# CPU_Power_XTAL_Prog.net
KiCad netlist of a schematic drawn in Altium Designer
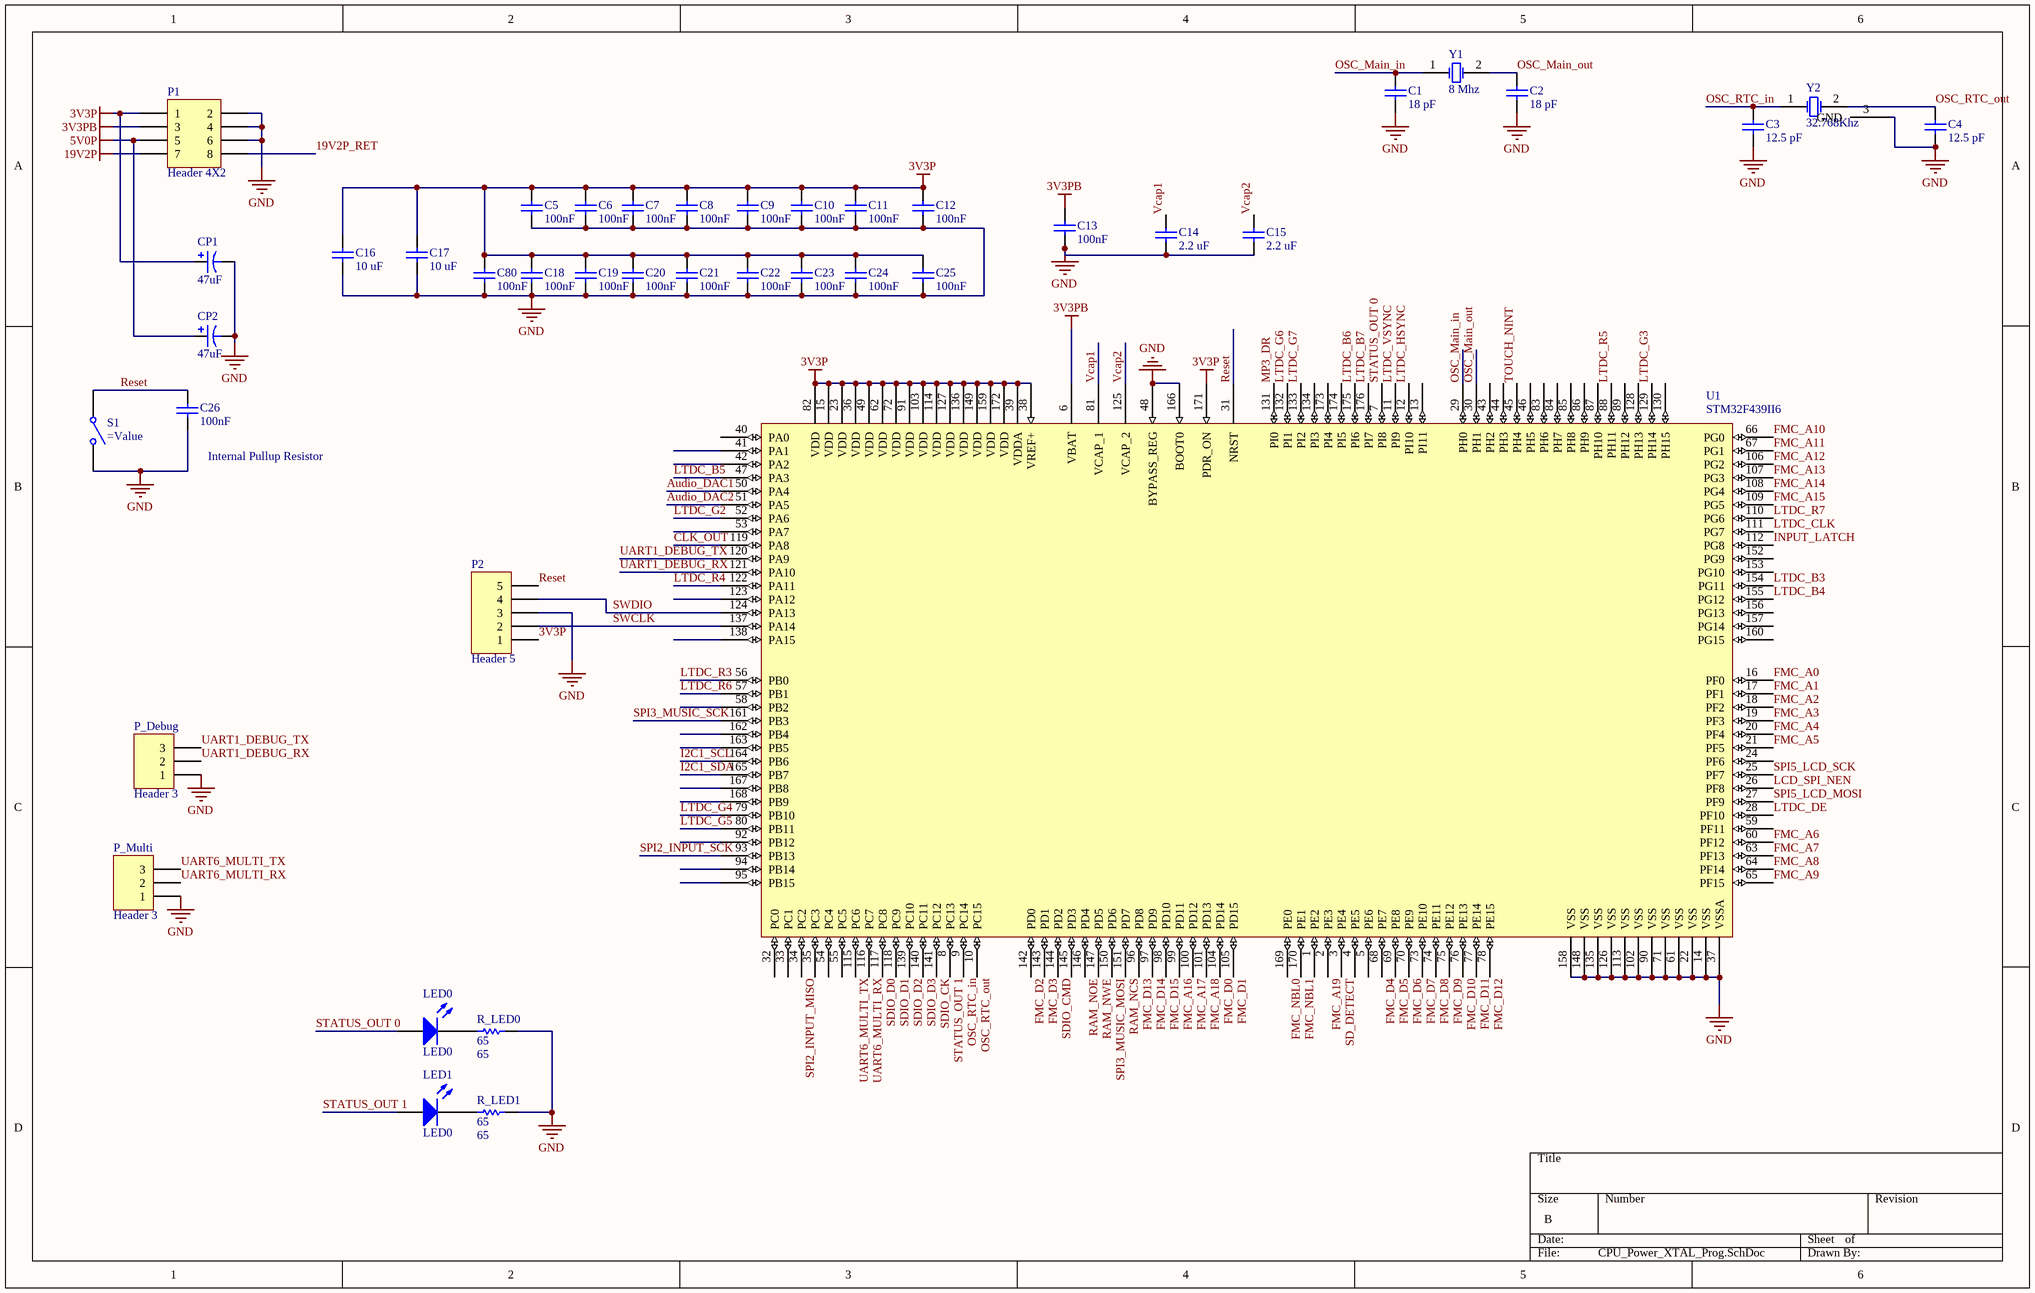
[diagram p0: CPU_Power_XTAL_Prog.SchDoc]

(export (version "E")
  (design (tool "Eeschema 10.0.6"))
  (components
    (comp (ref "C1")
      (value "18 pF")
      (footprint "C0805")
      (description "Capacitor")
      (fields (field (name "PUBLISHER") "Altium Limited"))
      (libsource (lib "Miscellaneous Devices") (part "Cap"))
    )
    (comp (ref "C2")
      (value "18 pF")
      (footprint "C0805")
      (description "Capacitor")
      (fields (field (name "PUBLISHER") "Altium Limited"))
      (libsource (lib "Miscellaneous Devices") (part "Cap"))
    )
    (comp (ref "C3")
      (value "12.5 pF")
      (footprint "C0805")
      (description "Capacitor")
      (fields (field (name "PUBLISHER") "Altium Limited"))
      (libsource (lib "Miscellaneous Devices") (part "Cap"))
    )
    (comp (ref "C4")
      (value "12.5 pF")
      (footprint "C0805")
      (description "Capacitor")
      (fields (field (name "PUBLISHER") "Altium Limited"))
      (libsource (lib "Miscellaneous Devices") (part "Cap"))
    )
    (comp (ref "C5")
      (value "100nF")
      (footprint "C0805")
      (description "Capacitor")
      (fields (field (name "PUBLISHER") "Altium Limited"))
      (libsource (lib "Miscellaneous Devices") (part "Cap"))
    )
    (comp (ref "C6")
      (value "100nF")
      (footprint "C0805")
      (description "Capacitor")
      (fields (field (name "PUBLISHER") "Altium Limited"))
      (libsource (lib "Miscellaneous Devices") (part "Cap"))
    )
    (comp (ref "C7")
      (value "100nF")
      (footprint "C0805")
      (description "Capacitor")
      (fields (field (name "PUBLISHER") "Altium Limited"))
      (libsource (lib "Miscellaneous Devices") (part "Cap"))
    )
    (comp (ref "C8")
      (value "100nF")
      (footprint "C0805")
      (description "Capacitor")
      (fields (field (name "PUBLISHER") "Altium Limited"))
      (libsource (lib "Miscellaneous Devices") (part "Cap"))
    )
    (comp (ref "C9")
      (value "100nF")
      (footprint "C0805")
      (description "Capacitor")
      (fields (field (name "PUBLISHER") "Altium Limited"))
      (libsource (lib "Miscellaneous Devices") (part "Cap"))
    )
    (comp (ref "C10")
      (value "100nF")
      (footprint "C0805")
      (description "Capacitor")
      (fields (field (name "PUBLISHER") "Altium Limited"))
      (libsource (lib "Miscellaneous Devices") (part "Cap"))
    )
    (comp (ref "C11")
      (value "100nF")
      (footprint "C0805")
      (description "Capacitor")
      (fields (field (name "PUBLISHER") "Altium Limited"))
      (libsource (lib "Miscellaneous Devices") (part "Cap"))
    )
    (comp (ref "C12")
      (value "100nF")
      (footprint "C0805")
      (description "Capacitor")
      (fields (field (name "PUBLISHER") "Altium Limited"))
      (libsource (lib "Miscellaneous Devices") (part "Cap"))
    )
    (comp (ref "C13")
      (value "100nF")
      (footprint "C0805")
      (description "Capacitor")
      (fields (field (name "PUBLISHER") "Altium Limited"))
      (libsource (lib "Miscellaneous Devices") (part "Cap"))
    )
    (comp (ref "C14")
      (value "2.2 uF")
      (footprint "C0805")
      (description "Capacitor")
      (fields (field (name "PUBLISHER") "Altium Limited"))
      (libsource (lib "Miscellaneous Devices") (part "Cap"))
    )
    (comp (ref "C15")
      (value "2.2 uF")
      (footprint "C0805")
      (description "Capacitor")
      (fields (field (name "PUBLISHER") "Altium Limited"))
      (libsource (lib "Miscellaneous Devices") (part "Cap"))
    )
    (comp (ref "C16")
      (value "10 uF")
      (footprint "C0805")
      (description "Capacitor")
      (fields (field (name "PUBLISHER") "Altium Limited"))
      (libsource (lib "Miscellaneous Devices") (part "Cap"))
    )
    (comp (ref "C17")
      (value "10 uF")
      (footprint "C0805")
      (description "Capacitor")
      (fields (field (name "PUBLISHER") "Altium Limited"))
      (libsource (lib "Miscellaneous Devices") (part "Cap"))
    )
    (comp (ref "C18")
      (value "100nF")
      (footprint "C0805")
      (description "Capacitor")
      (fields (field (name "PUBLISHER") "Altium Limited"))
      (libsource (lib "Miscellaneous Devices") (part "Cap"))
    )
    (comp (ref "C19")
      (value "100nF")
      (footprint "C0805")
      (description "Capacitor")
      (fields (field (name "PUBLISHER") "Altium Limited"))
      (libsource (lib "Miscellaneous Devices") (part "Cap"))
    )
    (comp (ref "C20")
      (value "100nF")
      (footprint "C0805")
      (description "Capacitor")
      (fields (field (name "PUBLISHER") "Altium Limited"))
      (libsource (lib "Miscellaneous Devices") (part "Cap"))
    )
    (comp (ref "C21")
      (value "100nF")
      (footprint "C0805")
      (description "Capacitor")
      (fields (field (name "PUBLISHER") "Altium Limited"))
      (libsource (lib "Miscellaneous Devices") (part "Cap"))
    )
    (comp (ref "C22")
      (value "100nF")
      (footprint "C0805")
      (description "Capacitor")
      (fields (field (name "PUBLISHER") "Altium Limited"))
      (libsource (lib "Miscellaneous Devices") (part "Cap"))
    )
    (comp (ref "C23")
      (value "100nF")
      (footprint "C0805")
      (description "Capacitor")
      (fields (field (name "PUBLISHER") "Altium Limited"))
      (libsource (lib "Miscellaneous Devices") (part "Cap"))
    )
    (comp (ref "C24")
      (value "100nF")
      (footprint "C0805")
      (description "Capacitor")
      (fields (field (name "PUBLISHER") "Altium Limited"))
      (libsource (lib "Miscellaneous Devices") (part "Cap"))
    )
    (comp (ref "C25")
      (value "100nF")
      (footprint "C0805")
      (description "Capacitor")
      (fields (field (name "PUBLISHER") "Altium Limited"))
      (libsource (lib "Miscellaneous Devices") (part "Cap"))
    )
    (comp (ref "C26")
      (value "100nF")
      (footprint "C0805")
      (description "Capacitor")
      (fields (field (name "PUBLISHER") "Altium Limited"))
      (libsource (lib "Miscellaneous Devices") (part "Cap"))
    )
    (comp (ref "C80")
      (value "100nF")
      (footprint "C0805")
      (description "Capacitor")
      (fields (field (name "PUBLISHER") "Altium Limited"))
      (libsource (lib "Miscellaneous Devices") (part "Cap"))
    )
    (comp (ref "CP1")
      (value "47uF")
      (footprint "KemetC3")
      (description "Polarized Capacitor (Radial)")
      (fields (field (name "PUBLISHER") "Altium Limited"))
      (libsource (lib "Miscellaneous Devices") (part "Cap Pol1"))
    )
    (comp (ref "CP2")
      (value "47uF")
      (footprint "KemetC3")
      (description "Polarized Capacitor (Radial)")
      (fields (field (name "PUBLISHER") "Altium Limited"))
      (libsource (lib "Miscellaneous Devices") (part "Cap Pol1"))
    )
    (comp (ref "LED0")
      (value "LED0")
      (footprint "LED-LTST")
      (description "Typical INFRARED GaAs LED")
      (fields (field (name "PUBLISHER") "Altium Limited"))
      (libsource (lib "Miscellaneous Devices") (part "LED0"))
    )
    (comp (ref "LED1")
      (value "LED0")
      (footprint "LED-LTST")
      (description "Typical INFRARED GaAs LED")
      (fields (field (name "PUBLISHER") "Altium Limited"))
      (libsource (lib "Miscellaneous Devices") (part "LED0"))
    )
    (comp (ref "P1")
      (value "Header 4X2")
      (footprint "Molex MiniFit Jr8")
      (description "Header, 4-Pin, Dual row")
      (fields (field (name "PUBLISHER") "Altium Limited"))
      (libsource (lib "Miscellaneous Connectors") (part "Header 4X2"))
    )
    (comp (ref "P2")
      (value "Header 5")
      (footprint "HDR1X5")
      (description "Header, 5-Pin")
      (fields (field (name "PUBLISHER") "Altium Limited"))
      (libsource (lib "Miscellaneous Connectors") (part "Header 5"))
    )
    (comp (ref "P_Debug")
      (value "Header 3")
      (footprint "HDR1X3")
      (description "Header, 3-Pin")
      (fields (field (name "PUBLISHER") "Altium Limited"))
      (libsource (lib "Miscellaneous Connectors") (part "Header 3"))
    )
    (comp (ref "P_Multi")
      (value "Header 3")
      (footprint "HDR1X3")
      (description "Header, 3-Pin")
      (fields (field (name "PUBLISHER") "Altium Limited"))
      (libsource (lib "Miscellaneous Connectors") (part "Header 3"))
    )
    (comp (ref "R_LED0")
      (value "65")
      (footprint "6-0805_M")
      (description "Resistor")
      (fields (field (name "ALTIUM_VALUE") "65") (field (name "PUBLISHER") "Altium Limited"))
      (libsource (lib "Miscellaneous Devices") (part "Res1"))
    )
    (comp (ref "R_LED1")
      (value "65")
      (footprint "6-0805_M")
      (description "Resistor")
      (fields (field (name "ALTIUM_VALUE") "65") (field (name "PUBLISHER") "Altium Limited"))
      (libsource (lib "Miscellaneous Devices") (part "Res1"))
    )
    (comp (ref "S1")
      (value "~")
      (footprint "Reset_Button")
      (description "Single-Pole, Single-Throw Switch")
      (fields (field (name "PUBLISHER") "Altium Limited"))
      (libsource (lib "Miscellaneous Devices") (part "SW-SPST"))
    )
    (comp (ref "U1")
      (value "STM32F439II6")
      (footprint "LQFP76")
      (description "Arm Cortex M4 Processor")
      (libsource (lib "GameMan") (part "STM32F439IIT6"))
    )
    (comp (ref "Y1")
      (value "8 Mhz")
      (footprint "HC-49U")
      (description "Crystal Oscillator")
      (fields (field (name "PUBLISHER") "Altium Limited"))
      (libsource (lib "Miscellaneous Devices") (part "XTAL"))
    )
    (comp (ref "Y2")
      (value "32.768Khz")
      (footprint "C-2Type Crystal")
      (description "Crystal Oscillator")
      (fields (field (name "PUBLISHER") "Altium Limited"))
      (libsource (lib "") (part "XTAL_1"))
    )
  )
  (nets
    (net (code "1") (name "/19V2P_RET") (class "Default")
      (node (ref "P1") (pin "8") (pinfunction "8_8") (pintype "passive"))
    )
    (net (code "2") (name "/Audio_DAC1") (class "Default")
      (node (ref "U1") (pin "50") (pinfunction "PA4_50") (pintype "bidirectional"))
    )
    (net (code "3") (name "/Audio_DAC2") (class "Default")
      (node (ref "U1") (pin "51") (pinfunction "PA5_51") (pintype "bidirectional"))
    )
    (net (code "4") (name "/CLK_OUT") (class "Default")
      (node (ref "U1") (pin "119") (pinfunction "PA8_119") (pintype "bidirectional"))
    )
    (net (code "5") (name "/FMC_A0") (class "Default")
      (node (ref "U1") (pin "16") (pinfunction "PF0_16") (pintype "bidirectional"))
    )
    (net (code "6") (name "/FMC_A1") (class "Default")
      (node (ref "U1") (pin "17") (pinfunction "PF1_17") (pintype "bidirectional"))
    )
    (net (code "7") (name "/FMC_A2") (class "Default")
      (node (ref "U1") (pin "18") (pinfunction "PF2_18") (pintype "bidirectional"))
    )
    (net (code "8") (name "/FMC_A3") (class "Default")
      (node (ref "U1") (pin "19") (pinfunction "PF3_19") (pintype "bidirectional"))
    )
    (net (code "9") (name "/FMC_A4") (class "Default")
      (node (ref "U1") (pin "20") (pinfunction "PF4_20") (pintype "bidirectional"))
    )
    (net (code "10") (name "/FMC_A5") (class "Default")
      (node (ref "U1") (pin "21") (pinfunction "PF5_21") (pintype "bidirectional"))
    )
    (net (code "11") (name "/FMC_A6") (class "Default")
      (node (ref "U1") (pin "60") (pinfunction "PF12_60") (pintype "bidirectional"))
    )
    (net (code "12") (name "/FMC_A7") (class "Default")
      (node (ref "U1") (pin "63") (pinfunction "PF13_63") (pintype "bidirectional"))
    )
    (net (code "13") (name "/FMC_A8") (class "Default")
      (node (ref "U1") (pin "64") (pinfunction "PF14_64") (pintype "bidirectional"))
    )
    (net (code "14") (name "/FMC_A9") (class "Default")
      (node (ref "U1") (pin "65") (pinfunction "PF15_65") (pintype "bidirectional"))
    )
    (net (code "15") (name "/FMC_A10") (class "Default")
      (node (ref "U1") (pin "66") (pinfunction "PG0_66") (pintype "bidirectional"))
    )
    (net (code "16") (name "/FMC_A11") (class "Default")
      (node (ref "U1") (pin "67") (pinfunction "PG1_67") (pintype "bidirectional"))
    )
    (net (code "17") (name "/FMC_A12") (class "Default")
      (node (ref "U1") (pin "106") (pinfunction "PG2_106") (pintype "bidirectional"))
    )
    (net (code "18") (name "/FMC_A13") (class "Default")
      (node (ref "U1") (pin "107") (pinfunction "PG3_107") (pintype "bidirectional"))
    )
    (net (code "19") (name "/FMC_A14") (class "Default")
      (node (ref "U1") (pin "108") (pinfunction "PG4_108") (pintype "bidirectional"))
    )
    (net (code "20") (name "/FMC_A15") (class "Default")
      (node (ref "U1") (pin "109") (pinfunction "PG5_109") (pintype "bidirectional"))
    )
    (net (code "21") (name "/FMC_A16") (class "Default")
      (node (ref "U1") (pin "99") (pinfunction "PD11_99") (pintype "bidirectional"))
    )
    (net (code "22") (name "/FMC_A17") (class "Default")
      (node (ref "U1") (pin "100") (pinfunction "PD12_100") (pintype "bidirectional"))
    )
    (net (code "23") (name "/FMC_A18") (class "Default")
      (node (ref "U1") (pin "101") (pinfunction "PD13_101") (pintype "bidirectional"))
    )
    (net (code "24") (name "/FMC_A19") (class "Default")
      (node (ref "U1") (pin "2") (pinfunction "PE3_2") (pintype "bidirectional"))
    )
    (net (code "25") (name "/FMC_D0") (class "Default")
      (node (ref "U1") (pin "104") (pinfunction "PD14_104") (pintype "bidirectional"))
    )
    (net (code "26") (name "/FMC_D1") (class "Default")
      (node (ref "U1") (pin "105") (pinfunction "PD15_105") (pintype "bidirectional"))
    )
    (net (code "27") (name "/FMC_D2") (class "Default")
      (node (ref "U1") (pin "142") (pinfunction "PD0_142") (pintype "bidirectional"))
    )
    (net (code "28") (name "/FMC_D3") (class "Default")
      (node (ref "U1") (pin "143") (pinfunction "PD1_143") (pintype "bidirectional"))
    )
    (net (code "29") (name "/FMC_D4") (class "Default")
      (node (ref "U1") (pin "68") (pinfunction "PE7_68") (pintype "bidirectional"))
    )
    (net (code "30") (name "/FMC_D5") (class "Default")
      (node (ref "U1") (pin "69") (pinfunction "PE8_69") (pintype "bidirectional"))
    )
    (net (code "31") (name "/FMC_D6") (class "Default")
      (node (ref "U1") (pin "70") (pinfunction "PE9_70") (pintype "bidirectional"))
    )
    (net (code "32") (name "/FMC_D7") (class "Default")
      (node (ref "U1") (pin "73") (pinfunction "PE10_73") (pintype "bidirectional"))
    )
    (net (code "33") (name "/FMC_D8") (class "Default")
      (node (ref "U1") (pin "74") (pinfunction "PE11_74") (pintype "bidirectional"))
    )
    (net (code "34") (name "/FMC_D9") (class "Default")
      (node (ref "U1") (pin "75") (pinfunction "PE12_75") (pintype "bidirectional"))
    )
    (net (code "35") (name "/FMC_D10") (class "Default")
      (node (ref "U1") (pin "76") (pinfunction "PE13_76") (pintype "bidirectional"))
    )
    (net (code "36") (name "/FMC_D11") (class "Default")
      (node (ref "U1") (pin "77") (pinfunction "PE14_77") (pintype "bidirectional"))
    )
    (net (code "37") (name "/FMC_D12") (class "Default")
      (node (ref "U1") (pin "78") (pinfunction "PE15_78") (pintype "bidirectional"))
    )
    (net (code "38") (name "/FMC_D13") (class "Default")
      (node (ref "U1") (pin "96") (pinfunction "PD8_96") (pintype "bidirectional"))
    )
    (net (code "39") (name "/FMC_D14") (class "Default")
      (node (ref "U1") (pin "97") (pinfunction "PD9_97") (pintype "bidirectional"))
    )
    (net (code "40") (name "/FMC_D15") (class "Default")
      (node (ref "U1") (pin "98") (pinfunction "PD10_98") (pintype "bidirectional"))
    )
    (net (code "41") (name "/FMC_NBL0") (class "Default")
      (node (ref "U1") (pin "169") (pinfunction "PE0_169") (pintype "bidirectional"))
    )
    (net (code "42") (name "/FMC_NBL1") (class "Default")
      (node (ref "U1") (pin "170") (pinfunction "PE1_170") (pintype "bidirectional"))
    )
    (net (code "43") (name "/I2C1_SCL") (class "Default")
      (node (ref "U1") (pin "164") (pinfunction "PB6_164") (pintype "bidirectional"))
    )
    (net (code "44") (name "/I2C1_SDA") (class "Default")
      (node (ref "U1") (pin "165") (pinfunction "PB7_165") (pintype "bidirectional"))
    )
    (net (code "45") (name "/INPUT_LATCH") (class "Default")
      (node (ref "U1") (pin "112") (pinfunction "PG8_112") (pintype "bidirectional"))
    )
    (net (code "46") (name "/LCD_SPI_NEN") (class "Default")
      (node (ref "U1") (pin "26") (pinfunction "PF8_26") (pintype "bidirectional"))
    )
    (net (code "47") (name "/LTDC_B3") (class "Default")
      (node (ref "U1") (pin "154") (pinfunction "PG11_154") (pintype "bidirectional"))
    )
    (net (code "48") (name "/LTDC_B4") (class "Default")
      (node (ref "U1") (pin "155") (pinfunction "PG12_155") (pintype "bidirectional"))
    )
    (net (code "49") (name "/LTDC_B5") (class "Default")
      (node (ref "U1") (pin "47") (pinfunction "PA3_47") (pintype "bidirectional"))
    )
    (net (code "50") (name "/LTDC_B6") (class "Default")
      (node (ref "U1") (pin "175") (pinfunction "PI6_175") (pintype "bidirectional"))
    )
    (net (code "51") (name "/LTDC_B7") (class "Default")
      (node (ref "U1") (pin "176") (pinfunction "PI7_176") (pintype "bidirectional"))
    )
    (net (code "52") (name "/LTDC_CLK") (class "Default")
      (node (ref "U1") (pin "111") (pinfunction "PG7_111") (pintype "bidirectional"))
    )
    (net (code "53") (name "/LTDC_DE") (class "Default")
      (node (ref "U1") (pin "28") (pinfunction "PF10_28") (pintype "bidirectional"))
    )
    (net (code "54") (name "/LTDC_G2") (class "Default")
      (node (ref "U1") (pin "52") (pinfunction "PA6_52") (pintype "bidirectional"))
    )
    (net (code "55") (name "/LTDC_G3") (class "Default")
      (node (ref "U1") (pin "129") (pinfunction "PH14_129") (pintype "bidirectional"))
    )
    (net (code "56") (name "/LTDC_G4") (class "Default")
      (node (ref "U1") (pin "79") (pinfunction "PB10_79") (pintype "bidirectional"))
    )
    (net (code "57") (name "/LTDC_G5") (class "Default")
      (node (ref "U1") (pin "80") (pinfunction "PB11_80") (pintype "bidirectional"))
    )
    (net (code "58") (name "/LTDC_G6") (class "Default")
      (node (ref "U1") (pin "132") (pinfunction "PI1_132") (pintype "bidirectional"))
    )
    (net (code "59") (name "/LTDC_G7") (class "Default")
      (node (ref "U1") (pin "133") (pinfunction "PI2_133") (pintype "bidirectional"))
    )
    (net (code "60") (name "/LTDC_HSYNC") (class "Default")
      (node (ref "U1") (pin "12") (pinfunction "PI10_12") (pintype "bidirectional"))
    )
    (net (code "61") (name "/LTDC_R3") (class "Default")
      (node (ref "U1") (pin "56") (pinfunction "PB0_56") (pintype "bidirectional"))
    )
    (net (code "62") (name "/LTDC_R4") (class "Default")
      (node (ref "U1") (pin "122") (pinfunction "PA11_122") (pintype "bidirectional"))
    )
    (net (code "63") (name "/LTDC_R5") (class "Default")
      (node (ref "U1") (pin "88") (pinfunction "PH11_88") (pintype "bidirectional"))
    )
    (net (code "64") (name "/LTDC_R6") (class "Default")
      (node (ref "U1") (pin "57") (pinfunction "PB1_57") (pintype "bidirectional"))
    )
    (net (code "65") (name "/LTDC_R7") (class "Default")
      (node (ref "U1") (pin "110") (pinfunction "PG6_110") (pintype "bidirectional"))
    )
    (net (code "66") (name "/LTDC_VSYNC") (class "Default")
      (node (ref "U1") (pin "11") (pinfunction "PI9_11") (pintype "bidirectional"))
    )
    (net (code "67") (name "/MP3_DR") (class "Default")
      (node (ref "U1") (pin "131") (pinfunction "PI0_131") (pintype "bidirectional"))
    )
    (net (code "68") (name "/OSC_Main_in") (class "Default")
      (node (ref "C1") (pin "2") (pinfunction "2_2") (pintype "passive"))
      (node (ref "U1") (pin "29") (pinfunction "PH0_29") (pintype "bidirectional"))
      (node (ref "Y1") (pin "1") (pinfunction "OSC1_1") (pintype "passive"))
    )
    (net (code "69") (name "/OSC_Main_out") (class "Default")
      (node (ref "C2") (pin "2") (pinfunction "2_2") (pintype "passive"))
      (node (ref "U1") (pin "30") (pinfunction "PH1_30") (pintype "bidirectional"))
      (node (ref "Y1") (pin "2") (pinfunction "OSC2_2") (pintype "passive"))
    )
    (net (code "70") (name "/OSC_RTC_in") (class "Default")
      (node (ref "C3") (pin "2") (pinfunction "2_2") (pintype "passive"))
      (node (ref "U1") (pin "9") (pinfunction "PC14_9") (pintype "bidirectional"))
      (node (ref "Y2") (pin "1") (pinfunction "OSC1_1") (pintype "passive"))
    )
    (net (code "71") (name "/OSC_RTC_out") (class "Default")
      (node (ref "C4") (pin "2") (pinfunction "2_2") (pintype "passive"))
      (node (ref "U1") (pin "10") (pinfunction "PC15_10") (pintype "bidirectional"))
      (node (ref "Y2") (pin "2") (pinfunction "OSC2_2") (pintype "passive"))
    )
    (net (code "72") (name "/RAM_NCS") (class "Default")
      (node (ref "U1") (pin "151") (pinfunction "PD7_151") (pintype "bidirectional"))
    )
    (net (code "73") (name "/RAM_NOE") (class "Default")
      (node (ref "U1") (pin "146") (pinfunction "PD4_146") (pintype "bidirectional"))
    )
    (net (code "74") (name "/RAM_NWE") (class "Default")
      (node (ref "U1") (pin "147") (pinfunction "PD5_147") (pintype "bidirectional"))
    )
    (net (code "75") (name "/Reset") (class "Default")
      (node (ref "C26") (pin "2") (pinfunction "2_2") (pintype "passive"))
      (node (ref "P2") (pin "5") (pinfunction "5_5") (pintype "passive"))
      (node (ref "S1") (pin "0") (pinfunction "COMMON_0") (pintype "passive"))
      (node (ref "U1") (pin "31") (pinfunction "NRST_31") (pintype "power_in"))
    )
    (net (code "76") (name "/SDIO_CK") (class "Default")
      (node (ref "U1") (pin "141") (pinfunction "PC12_141") (pintype "bidirectional"))
    )
    (net (code "77") (name "/SDIO_CMD") (class "Default")
      (node (ref "U1") (pin "144") (pinfunction "PD2_144") (pintype "bidirectional"))
    )
    (net (code "78") (name "/SDIO_D0") (class "Default")
      (node (ref "U1") (pin "117") (pinfunction "PC8_117") (pintype "bidirectional"))
    )
    (net (code "79") (name "/SDIO_D1") (class "Default")
      (node (ref "U1") (pin "118") (pinfunction "PC9_118") (pintype "bidirectional"))
    )
    (net (code "80") (name "/SDIO_D2") (class "Default")
      (node (ref "U1") (pin "139") (pinfunction "PC10_139") (pintype "bidirectional"))
    )
    (net (code "81") (name "/SDIO_D3") (class "Default")
      (node (ref "U1") (pin "140") (pinfunction "PC11_140") (pintype "bidirectional"))
    )
    (net (code "82") (name "/SD_DETECT") (class "Default")
      (node (ref "U1") (pin "3") (pinfunction "PE4_3") (pintype "bidirectional"))
    )
    (net (code "83") (name "/SPI2_INPUT_MISO") (class "Default")
      (node (ref "U1") (pin "34") (pinfunction "PC2_34") (pintype "bidirectional"))
    )
    (net (code "84") (name "/SPI2_INPUT_SCK") (class "Default")
      (node (ref "U1") (pin "93") (pinfunction "PB13_93") (pintype "bidirectional"))
    )
    (net (code "85") (name "/SPI3_MUSIC_MOSI") (class "Default")
      (node (ref "U1") (pin "150") (pinfunction "PD6_150") (pintype "bidirectional"))
    )
    (net (code "86") (name "/SPI3_MUSIC_SCK") (class "Default")
      (node (ref "U1") (pin "161") (pinfunction "PB3_161") (pintype "bidirectional"))
    )
    (net (code "87") (name "/SPI5_LCD_MOSI") (class "Default")
      (node (ref "U1") (pin "27") (pinfunction "PF9_27") (pintype "bidirectional"))
    )
    (net (code "88") (name "/SPI5_LCD_SCK") (class "Default")
      (node (ref "U1") (pin "25") (pinfunction "PF7_25") (pintype "bidirectional"))
    )
    (net (code "89") (name "/STATUS_OUT 0") (class "Default")
      (node (ref "LED0") (pin "A") (pinfunction "A_A") (pintype "passive"))
      (node (ref "U1") (pin "7") (pinfunction "PI8_7") (pintype "bidirectional"))
    )
    (net (code "90") (name "/STATUS_OUT 1") (class "Default")
      (node (ref "LED1") (pin "A") (pinfunction "A_A") (pintype "passive"))
      (node (ref "U1") (pin "8") (pinfunction "PC13_8") (pintype "bidirectional"))
    )
    (net (code "91") (name "/SWCLK") (class "Default")
      (node (ref "P2") (pin "2") (pinfunction "2_2") (pintype "passive"))
      (node (ref "U1") (pin "137") (pinfunction "PA14_137") (pintype "bidirectional"))
    )
    (net (code "92") (name "/SWDIO") (class "Default")
      (node (ref "P2") (pin "4") (pinfunction "4_4") (pintype "passive"))
      (node (ref "U1") (pin "124") (pinfunction "PA13_124") (pintype "bidirectional"))
    )
    (net (code "93") (name "/TOUCH_NINT") (class "Default")
      (node (ref "U1") (pin "45") (pinfunction "PH4_45") (pintype "bidirectional"))
    )
    (net (code "94") (name "/UART1_DEBUG_RX") (class "Default")
      (node (ref "P_Debug") (pin "2") (pinfunction "2_2") (pintype "passive"))
      (node (ref "U1") (pin "121") (pinfunction "PA10_121") (pintype "bidirectional"))
    )
    (net (code "95") (name "/UART1_DEBUG_TX") (class "Default")
      (node (ref "P_Debug") (pin "3") (pinfunction "3_3") (pintype "passive"))
      (node (ref "U1") (pin "120") (pinfunction "PA9_120") (pintype "bidirectional"))
    )
    (net (code "96") (name "/UART6_MULTI_RX") (class "Default")
      (node (ref "P_Multi") (pin "2") (pinfunction "2_2") (pintype "passive"))
      (node (ref "U1") (pin "116") (pinfunction "PC7_116") (pintype "bidirectional"))
    )
    (net (code "97") (name "/UART6_MULTI_TX") (class "Default")
      (node (ref "P_Multi") (pin "3") (pinfunction "3_3") (pintype "passive"))
      (node (ref "U1") (pin "115") (pinfunction "PC6_115") (pintype "bidirectional"))
    )
    (net (code "98") (name "/Vcap1") (class "Default")
      (node (ref "C14") (pin "1") (pinfunction "1_1") (pintype "passive"))
      (node (ref "U1") (pin "81") (pinfunction "VCAP_1_81") (pintype "passive"))
    )
    (net (code "99") (name "/Vcap2") (class "Default")
      (node (ref "C15") (pin "1") (pinfunction "1_1") (pintype "passive"))
      (node (ref "U1") (pin "125") (pinfunction "VCAP_2_125") (pintype "passive"))
    )
    (net (code "100") (name "3V3P") (class "Default")
      (node (ref "C10") (pin "2") (pinfunction "2_2") (pintype "passive"))
      (node (ref "C11") (pin "2") (pinfunction "2_2") (pintype "passive"))
      (node (ref "C12") (pin "2") (pinfunction "2_2") (pintype "passive"))
      (node (ref "C16") (pin "2") (pinfunction "2_2") (pintype "passive"))
      (node (ref "C17") (pin "2") (pinfunction "2_2") (pintype "passive"))
      (node (ref "C18") (pin "2") (pinfunction "2_2") (pintype "passive"))
      (node (ref "C19") (pin "2") (pinfunction "2_2") (pintype "passive"))
      (node (ref "C20") (pin "2") (pinfunction "2_2") (pintype "passive"))
      (node (ref "C21") (pin "2") (pinfunction "2_2") (pintype "passive"))
      (node (ref "C22") (pin "2") (pinfunction "2_2") (pintype "passive"))
      (node (ref "C23") (pin "2") (pinfunction "2_2") (pintype "passive"))
      (node (ref "C24") (pin "2") (pinfunction "2_2") (pintype "passive"))
      (node (ref "C25") (pin "2") (pinfunction "2_2") (pintype "passive"))
      (node (ref "C5") (pin "2") (pinfunction "2_2") (pintype "passive"))
      (node (ref "C6") (pin "2") (pinfunction "2_2") (pintype "passive"))
      (node (ref "C7") (pin "2") (pinfunction "2_2") (pintype "passive"))
      (node (ref "C8") (pin "2") (pinfunction "2_2") (pintype "passive"))
      (node (ref "C80") (pin "2") (pinfunction "2_2") (pintype "passive"))
      (node (ref "C9") (pin "2") (pinfunction "2_2") (pintype "passive"))
      (node (ref "CP1") (pin "2") (pinfunction "1_2") (pintype "passive"))
      (node (ref "P1") (pin "1") (pinfunction "1_1") (pintype "passive"))
      (node (ref "P2") (pin "1") (pinfunction "1_1") (pintype "passive"))
      (node (ref "U1") (pin "103") (pinfunction "VDD_103") (pintype "power_in"))
      (node (ref "U1") (pin "114") (pinfunction "VDD_114") (pintype "power_in"))
      (node (ref "U1") (pin "127") (pinfunction "VDD_127") (pintype "passive"))
      (node (ref "U1") (pin "136") (pinfunction "VDD_136") (pintype "passive"))
      (node (ref "U1") (pin "149") (pinfunction "VDD_149") (pintype "passive"))
      (node (ref "U1") (pin "15") (pinfunction "VDD_15") (pintype "power_in"))
      (node (ref "U1") (pin "159") (pinfunction "VDD_159") (pintype "power_in"))
      (node (ref "U1") (pin "171") (pinfunction "PDR_ON_171") (pintype "input"))
      (node (ref "U1") (pin "172") (pinfunction "VDD_172") (pintype "power_in"))
      (node (ref "U1") (pin "23") (pinfunction "VDD_23") (pintype "power_in"))
      (node (ref "U1") (pin "36") (pinfunction "VDD_36") (pintype "power_in"))
      (node (ref "U1") (pin "38") (pinfunction "VREF+_38") (pintype "input"))
      (node (ref "U1") (pin "39") (pinfunction "VDDA_39") (pintype "power_in"))
      (node (ref "U1") (pin "49") (pinfunction "VDD_49") (pintype "power_in"))
      (node (ref "U1") (pin "62") (pinfunction "VDD_62") (pintype "power_in"))
      (node (ref "U1") (pin "72") (pinfunction "VDD_72") (pintype "power_in"))
      (node (ref "U1") (pin "82") (pinfunction "VDD_82") (pintype "power_in"))
      (node (ref "U1") (pin "91") (pinfunction "VDD_91") (pintype "power_in"))
    )
    (net (code "101") (name "3V3PB") (class "Default")
      (node (ref "C13") (pin "1") (pinfunction "1_1") (pintype "passive"))
      (node (ref "P1") (pin "3") (pinfunction "3_3") (pintype "passive"))
      (node (ref "U1") (pin "6") (pinfunction "VBAT_6") (pintype "power_in"))
    )
    (net (code "102") (name "5V0P") (class "Default")
      (node (ref "CP2") (pin "2") (pinfunction "1_2") (pintype "passive"))
      (node (ref "P1") (pin "5") (pinfunction "5_5") (pintype "passive"))
    )
    (net (code "103") (name "19V2P") (class "Default")
      (node (ref "P1") (pin "7") (pinfunction "7_7") (pintype "passive"))
    )
    (net (code "104") (name "GND") (class "Default")
      (node (ref "C1") (pin "1") (pinfunction "1_1") (pintype "passive"))
      (node (ref "C10") (pin "1") (pinfunction "1_1") (pintype "passive"))
      (node (ref "C11") (pin "1") (pinfunction "1_1") (pintype "passive"))
      (node (ref "C12") (pin "1") (pinfunction "1_1") (pintype "passive"))
      (node (ref "C13") (pin "2") (pinfunction "2_2") (pintype "passive"))
      (node (ref "C14") (pin "2") (pinfunction "2_2") (pintype "passive"))
      (node (ref "C15") (pin "2") (pinfunction "2_2") (pintype "passive"))
      (node (ref "C16") (pin "1") (pinfunction "1_1") (pintype "passive"))
      (node (ref "C17") (pin "1") (pinfunction "1_1") (pintype "passive"))
      (node (ref "C18") (pin "1") (pinfunction "1_1") (pintype "passive"))
      (node (ref "C19") (pin "1") (pinfunction "1_1") (pintype "passive"))
      (node (ref "C2") (pin "1") (pinfunction "1_1") (pintype "passive"))
      (node (ref "C20") (pin "1") (pinfunction "1_1") (pintype "passive"))
      (node (ref "C21") (pin "1") (pinfunction "1_1") (pintype "passive"))
      (node (ref "C22") (pin "1") (pinfunction "1_1") (pintype "passive"))
      (node (ref "C23") (pin "1") (pinfunction "1_1") (pintype "passive"))
      (node (ref "C24") (pin "1") (pinfunction "1_1") (pintype "passive"))
      (node (ref "C25") (pin "1") (pinfunction "1_1") (pintype "passive"))
      (node (ref "C26") (pin "1") (pinfunction "1_1") (pintype "passive"))
      (node (ref "C3") (pin "1") (pinfunction "1_1") (pintype "passive"))
      (node (ref "C4") (pin "1") (pinfunction "1_1") (pintype "passive"))
      (node (ref "C5") (pin "1") (pinfunction "1_1") (pintype "passive"))
      (node (ref "C6") (pin "1") (pinfunction "1_1") (pintype "passive"))
      (node (ref "C7") (pin "1") (pinfunction "1_1") (pintype "passive"))
      (node (ref "C8") (pin "1") (pinfunction "1_1") (pintype "passive"))
      (node (ref "C80") (pin "1") (pinfunction "1_1") (pintype "passive"))
      (node (ref "C9") (pin "1") (pinfunction "1_1") (pintype "passive"))
      (node (ref "CP1") (pin "1") (pinfunction "2_1") (pintype "passive"))
      (node (ref "CP2") (pin "1") (pinfunction "2_1") (pintype "passive"))
      (node (ref "P1") (pin "2") (pinfunction "2_2") (pintype "passive"))
      (node (ref "P1") (pin "4") (pinfunction "4_4") (pintype "passive"))
      (node (ref "P1") (pin "6") (pinfunction "6_6") (pintype "passive"))
      (node (ref "P2") (pin "3") (pinfunction "3_3") (pintype "passive"))
      (node (ref "P_Debug") (pin "1") (pinfunction "1_1") (pintype "passive"))
      (node (ref "P_Multi") (pin "1") (pinfunction "1_1") (pintype "passive"))
      (node (ref "R_LED0") (pin "2") (pinfunction "2_2") (pintype "passive"))
      (node (ref "R_LED1") (pin "2") (pinfunction "2_2") (pintype "passive"))
      (node (ref "S1") (pin "1") (pinfunction "NO_1") (pintype "passive"))
      (node (ref "U1") (pin "102") (pinfunction "VSS_102") (pintype "power_in"))
      (node (ref "U1") (pin "113") (pinfunction "VSS_113") (pintype "power_in"))
      (node (ref "U1") (pin "126") (pinfunction "VSS_126") (pintype "passive"))
      (node (ref "U1") (pin "135") (pinfunction "VSS_135") (pintype "passive"))
      (node (ref "U1") (pin "14") (pinfunction "VSS_14") (pintype "power_in"))
      (node (ref "U1") (pin "148") (pinfunction "VSS_148") (pintype "passive"))
      (node (ref "U1") (pin "158") (pinfunction "VSS_158") (pintype "power_in"))
      (node (ref "U1") (pin "166") (pinfunction "BOOT0_166") (pintype "input"))
      (node (ref "U1") (pin "22") (pinfunction "VSS_22") (pintype "power_in"))
      (node (ref "U1") (pin "37") (pinfunction "VSSA_37") (pintype "power_in"))
      (node (ref "U1") (pin "48") (pinfunction "BYPASS_REG_48") (pintype "input"))
      (node (ref "U1") (pin "61") (pinfunction "VSS_61") (pintype "power_in"))
      (node (ref "U1") (pin "71") (pinfunction "VSS_71") (pintype "power_in"))
      (node (ref "U1") (pin "90") (pinfunction "VSS_90") (pintype "power_in"))
      (node (ref "Y2") (pin "3") (pinfunction "GND_3") (pintype "passive"))
    )
    (net (code "105") (name "Net-(LED0-PadK)") (class "Default")
      (node (ref "LED0") (pin "K") (pinfunction "K_K") (pintype "passive"))
      (node (ref "R_LED0") (pin "1") (pinfunction "1_1") (pintype "passive"))
    )
    (net (code "106") (name "Net-(LED1-PadK)") (class "Default")
      (node (ref "LED1") (pin "K") (pinfunction "K_K") (pintype "passive"))
      (node (ref "R_LED1") (pin "1") (pinfunction "1_1") (pintype "passive"))
    )
    (net (code "107") (name "unconnected-(U1-PA0-Pad40)") (class "Default")
      (node (ref "U1") (pin "40") (pinfunction "PA0_40") (pintype "bidirectional"))
    )
    (net (code "108") (name "unconnected-(U1-PA1-Pad41)") (class "Default")
      (node (ref "U1") (pin "41") (pinfunction "PA1_41") (pintype "bidirectional"))
    )
    (net (code "109") (name "unconnected-(U1-PA2-Pad42)") (class "Default")
      (node (ref "U1") (pin "42") (pinfunction "PA2_42") (pintype "bidirectional"))
    )
    (net (code "110") (name "unconnected-(U1-PA7-Pad53)") (class "Default")
      (node (ref "U1") (pin "53") (pinfunction "PA7_53") (pintype "bidirectional"))
    )
    (net (code "111") (name "unconnected-(U1-PA12-Pad123)") (class "Default")
      (node (ref "U1") (pin "123") (pinfunction "PA12_123") (pintype "bidirectional"))
    )
    (net (code "112") (name "unconnected-(U1-PA15-Pad138)") (class "Default")
      (node (ref "U1") (pin "138") (pinfunction "PA15_138") (pintype "bidirectional"))
    )
    (net (code "113") (name "unconnected-(U1-PB2-Pad58)") (class "Default")
      (node (ref "U1") (pin "58") (pinfunction "PB2_58") (pintype "bidirectional"))
    )
    (net (code "114") (name "unconnected-(U1-PB4-Pad162)") (class "Default")
      (node (ref "U1") (pin "162") (pinfunction "PB4_162") (pintype "bidirectional"))
    )
    (net (code "115") (name "unconnected-(U1-PB5-Pad163)") (class "Default")
      (node (ref "U1") (pin "163") (pinfunction "PB5_163") (pintype "bidirectional"))
    )
    (net (code "116") (name "unconnected-(U1-PB8-Pad167)") (class "Default")
      (node (ref "U1") (pin "167") (pinfunction "PB8_167") (pintype "bidirectional"))
    )
    (net (code "117") (name "unconnected-(U1-PB9-Pad168)") (class "Default")
      (node (ref "U1") (pin "168") (pinfunction "PB9_168") (pintype "bidirectional"))
    )
    (net (code "118") (name "unconnected-(U1-PB12-Pad92)") (class "Default")
      (node (ref "U1") (pin "92") (pinfunction "PB12_92") (pintype "bidirectional"))
    )
    (net (code "119") (name "unconnected-(U1-PB14-Pad94)") (class "Default")
      (node (ref "U1") (pin "94") (pinfunction "PB14_94") (pintype "bidirectional"))
    )
    (net (code "120") (name "unconnected-(U1-PB15-Pad95)") (class "Default")
      (node (ref "U1") (pin "95") (pinfunction "PB15_95") (pintype "bidirectional"))
    )
    (net (code "121") (name "unconnected-(U1-PC0-Pad32)") (class "Default")
      (node (ref "U1") (pin "32") (pinfunction "PC0_32") (pintype "bidirectional"))
    )
    (net (code "122") (name "unconnected-(U1-PC1-Pad33)") (class "Default")
      (node (ref "U1") (pin "33") (pinfunction "PC1_33") (pintype "bidirectional"))
    )
    (net (code "123") (name "unconnected-(U1-PC3-Pad35)") (class "Default")
      (node (ref "U1") (pin "35") (pinfunction "PC3_35") (pintype "bidirectional"))
    )
    (net (code "124") (name "unconnected-(U1-PC4-Pad54)") (class "Default")
      (node (ref "U1") (pin "54") (pinfunction "PC4_54") (pintype "bidirectional"))
    )
    (net (code "125") (name "unconnected-(U1-PC5-Pad55)") (class "Default")
      (node (ref "U1") (pin "55") (pinfunction "PC5_55") (pintype "bidirectional"))
    )
    (net (code "126") (name "unconnected-(U1-PD3-Pad145)") (class "Default")
      (node (ref "U1") (pin "145") (pinfunction "PD3_145") (pintype "bidirectional"))
    )
    (net (code "127") (name "unconnected-(U1-PE2-Pad1)") (class "Default")
      (node (ref "U1") (pin "1") (pinfunction "PE2_1") (pintype "bidirectional"))
    )
    (net (code "128") (name "unconnected-(U1-PE5-Pad4)") (class "Default")
      (node (ref "U1") (pin "4") (pinfunction "PE5_4") (pintype "bidirectional"))
    )
    (net (code "129") (name "unconnected-(U1-PE6-Pad5)") (class "Default")
      (node (ref "U1") (pin "5") (pinfunction "PE6_5") (pintype "bidirectional"))
    )
    (net (code "130") (name "unconnected-(U1-PF6-Pad24)") (class "Default")
      (node (ref "U1") (pin "24") (pinfunction "PF6_24") (pintype "bidirectional"))
    )
    (net (code "131") (name "unconnected-(U1-PF11-Pad59)") (class "Default")
      (node (ref "U1") (pin "59") (pinfunction "PF11_59") (pintype "bidirectional"))
    )
    (net (code "132") (name "unconnected-(U1-PG9-Pad152)") (class "Default")
      (node (ref "U1") (pin "152") (pinfunction "PG9_152") (pintype "bidirectional"))
    )
    (net (code "133") (name "unconnected-(U1-PG10-Pad153)") (class "Default")
      (node (ref "U1") (pin "153") (pinfunction "PG10_153") (pintype "bidirectional"))
    )
    (net (code "134") (name "unconnected-(U1-PG13-Pad156)") (class "Default")
      (node (ref "U1") (pin "156") (pinfunction "PG13_156") (pintype "bidirectional"))
    )
    (net (code "135") (name "unconnected-(U1-PG14-Pad157)") (class "Default")
      (node (ref "U1") (pin "157") (pinfunction "PG14_157") (pintype "bidirectional"))
    )
    (net (code "136") (name "unconnected-(U1-PG15-Pad160)") (class "Default")
      (node (ref "U1") (pin "160") (pinfunction "PG15_160") (pintype "bidirectional"))
    )
    (net (code "137") (name "unconnected-(U1-PH2-Pad43)") (class "Default")
      (node (ref "U1") (pin "43") (pinfunction "PH2_43") (pintype "bidirectional"))
    )
    (net (code "138") (name "unconnected-(U1-PH3-Pad44)") (class "Default")
      (node (ref "U1") (pin "44") (pinfunction "PH3_44") (pintype "bidirectional"))
    )
    (net (code "139") (name "unconnected-(U1-PH5-Pad46)") (class "Default")
      (node (ref "U1") (pin "46") (pinfunction "PH5_46") (pintype "bidirectional"))
    )
    (net (code "140") (name "unconnected-(U1-PH6-Pad83)") (class "Default")
      (node (ref "U1") (pin "83") (pinfunction "PH6_83") (pintype "bidirectional"))
    )
    (net (code "141") (name "unconnected-(U1-PH7-Pad84)") (class "Default")
      (node (ref "U1") (pin "84") (pinfunction "PH7_84") (pintype "bidirectional"))
    )
    (net (code "142") (name "unconnected-(U1-PH8-Pad85)") (class "Default")
      (node (ref "U1") (pin "85") (pinfunction "PH8_85") (pintype "bidirectional"))
    )
    (net (code "143") (name "unconnected-(U1-PH9-Pad86)") (class "Default")
      (node (ref "U1") (pin "86") (pinfunction "PH9_86") (pintype "bidirectional"))
    )
    (net (code "144") (name "unconnected-(U1-PH10-Pad87)") (class "Default")
      (node (ref "U1") (pin "87") (pinfunction "PH10_87") (pintype "bidirectional"))
    )
    (net (code "145") (name "unconnected-(U1-PH12-Pad89)") (class "Default")
      (node (ref "U1") (pin "89") (pinfunction "PH12_89") (pintype "bidirectional"))
    )
    (net (code "146") (name "unconnected-(U1-PH13-Pad128)") (class "Default")
      (node (ref "U1") (pin "128") (pinfunction "PH13_128") (pintype "bidirectional"))
    )
    (net (code "147") (name "unconnected-(U1-PH15-Pad130)") (class "Default")
      (node (ref "U1") (pin "130") (pinfunction "PH15_130") (pintype "bidirectional"))
    )
    (net (code "148") (name "unconnected-(U1-PI3-Pad134)") (class "Default")
      (node (ref "U1") (pin "134") (pinfunction "PI3_134") (pintype "bidirectional"))
    )
    (net (code "149") (name "unconnected-(U1-PI4-Pad173)") (class "Default")
      (node (ref "U1") (pin "173") (pinfunction "PI4_173") (pintype "bidirectional"))
    )
    (net (code "150") (name "unconnected-(U1-PI5-Pad174)") (class "Default")
      (node (ref "U1") (pin "174") (pinfunction "PI5_174") (pintype "bidirectional"))
    )
    (net (code "151") (name "unconnected-(U1-PI11-Pad13)") (class "Default")
      (node (ref "U1") (pin "13") (pinfunction "PI11_13") (pintype "bidirectional"))
    )
  )
)
